# digital_pot.net
KiCad netlist of a schematic drawn in Altium Designer
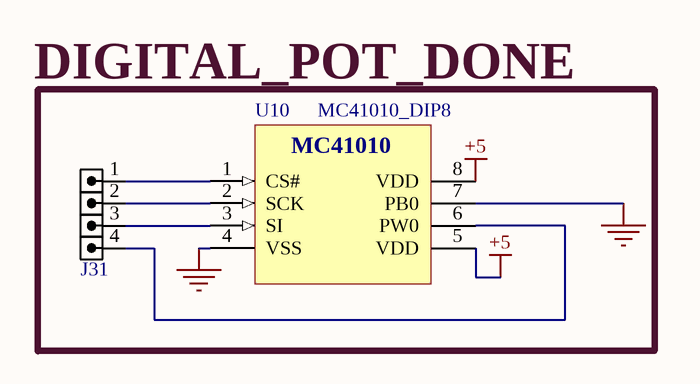
[diagram p0: digital_pot.SchDoc]

(export (version "E")
  (design (tool "Eeschema 10.0.6"))
  (components
    (comp (ref "J31")
      (value "HDR1X4")
      (footprint "HDR_M_1X4")
      (description "CONN, HEADER, Male, pitch: 2.54mm, 4POS")
      (libsource (lib "conn_header_2.54mm_st") (part "HDR_M_1X4"))
    )
    (comp (ref "U10")
      (value "MC41010_DIP8")
      (footprint "DIP_8")
      (description "CREATED BY J / Single/Dual Digital Potentiometer with SPI™ Interface")
      (fields (field (name "MANF") "MICROCHIP"))
      (libsource (lib "AvrDevelopmentBoard") (part "MCP41010_DIP8"))
    )
  )
  (nets
    (net (code "1") (name "+5") (class "Default")
      (node (ref "U10") (pin "5") (pinfunction "VDD_5") (pintype "passive"))
      (node (ref "U10") (pin "8") (pinfunction "VDD_8") (pintype "passive"))
    )
    (net (code "2") (name "GND") (class "Default")
      (node (ref "U10") (pin "4") (pinfunction "VSS_4") (pintype "passive"))
      (node (ref "U10") (pin "7") (pinfunction "PB0_7") (pintype "passive"))
    )
    (net (code "3") (name "Net-(U10-CS#)") (class "Default")
      (node (ref "J31") (pin "1") (pinfunction "1_1") (pintype "passive"))
      (node (ref "U10") (pin "1") (pinfunction "CS#_1") (pintype "input"))
    )
    (net (code "4") (name "Net-(U10-PW0)") (class "Default")
      (node (ref "J31") (pin "4") (pinfunction "4_4") (pintype "passive"))
      (node (ref "U10") (pin "6") (pinfunction "PW0_6") (pintype "passive"))
    )
    (net (code "5") (name "Net-(U10-SCK)") (class "Default")
      (node (ref "J31") (pin "2") (pinfunction "2_2") (pintype "passive"))
      (node (ref "U10") (pin "2") (pinfunction "SCK_2") (pintype "input"))
    )
    (net (code "6") (name "Net-(U10-SI)") (class "Default")
      (node (ref "J31") (pin "3") (pinfunction "3_3") (pintype "passive"))
      (node (ref "U10") (pin "3") (pinfunction "SI_3") (pintype "input"))
    )
  )
)
